# 3MMLedBreakoutForArduino.net
KiCad netlist of a schematic drawn in EAGLE
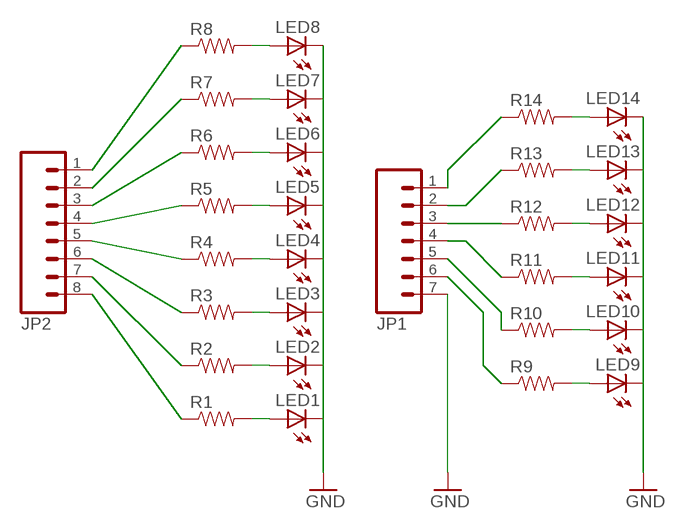
[diagram p0: schematic, sheet 1]

(export (version "E")
  (design (tool "Eeschema 10.0.6"))
  (components
    (comp (ref "JP1")
      (value "M07")
      (footprint "eagle-import:1X07")
      (libsource (lib "eagle-import") (part "M07"))
    )
    (comp (ref "JP2")
      (value "M081X08")
      (footprint "eagle-import:1X08")
      (libsource (lib "eagle-import") (part "M081X08"))
    )
    (comp (ref "LED1")
      (value "LED3MM")
      (footprint "eagle-import:LED3MM")
      (libsource (lib "eagle-import") (part "LED3MM"))
    )
    (comp (ref "LED2")
      (value "LED3MM")
      (footprint "eagle-import:LED3MM")
      (libsource (lib "eagle-import") (part "LED3MM"))
    )
    (comp (ref "LED3")
      (value "LED3MM")
      (footprint "eagle-import:LED3MM")
      (libsource (lib "eagle-import") (part "LED3MM"))
    )
    (comp (ref "LED4")
      (value "LED3MM")
      (footprint "eagle-import:LED3MM")
      (libsource (lib "eagle-import") (part "LED3MM"))
    )
    (comp (ref "LED5")
      (value "LED3MM")
      (footprint "eagle-import:LED3MM")
      (libsource (lib "eagle-import") (part "LED3MM"))
    )
    (comp (ref "LED6")
      (value "LED3MM")
      (footprint "eagle-import:LED3MM")
      (libsource (lib "eagle-import") (part "LED3MM"))
    )
    (comp (ref "LED7")
      (value "LED3MM")
      (footprint "eagle-import:LED3MM")
      (libsource (lib "eagle-import") (part "LED3MM"))
    )
    (comp (ref "LED8")
      (value "LED3MM")
      (footprint "eagle-import:LED3MM")
      (libsource (lib "eagle-import") (part "LED3MM"))
    )
    (comp (ref "LED9")
      (value "LED3MM")
      (footprint "eagle-import:LED3MM")
      (libsource (lib "eagle-import") (part "LED3MM"))
    )
    (comp (ref "LED10")
      (value "LED3MM")
      (footprint "eagle-import:LED3MM")
      (libsource (lib "eagle-import") (part "LED3MM"))
    )
    (comp (ref "LED11")
      (value "LED3MM")
      (footprint "eagle-import:LED3MM")
      (libsource (lib "eagle-import") (part "LED3MM"))
    )
    (comp (ref "LED12")
      (value "LED3MM")
      (footprint "eagle-import:LED3MM")
      (libsource (lib "eagle-import") (part "LED3MM"))
    )
    (comp (ref "LED13")
      (value "LED3MM")
      (footprint "eagle-import:LED3MM")
      (libsource (lib "eagle-import") (part "LED3MM"))
    )
    (comp (ref "LED14")
      (value "LED3MM")
      (footprint "eagle-import:LED3MM")
      (libsource (lib "eagle-import") (part "LED3MM"))
    )
    (comp (ref "R1")
      (value "RESISTORAXIAL-0.3")
      (footprint "eagle-import:AXIAL-0.3")
      (libsource (lib "eagle-import") (part "RESISTORAXIAL-0.3"))
    )
    (comp (ref "R2")
      (value "RESISTORAXIAL-0.3")
      (footprint "eagle-import:AXIAL-0.3")
      (libsource (lib "eagle-import") (part "RESISTORAXIAL-0.3"))
    )
    (comp (ref "R3")
      (value "RESISTORAXIAL-0.3")
      (footprint "eagle-import:AXIAL-0.3")
      (libsource (lib "eagle-import") (part "RESISTORAXIAL-0.3"))
    )
    (comp (ref "R4")
      (value "RESISTORAXIAL-0.3")
      (footprint "eagle-import:AXIAL-0.3")
      (libsource (lib "eagle-import") (part "RESISTORAXIAL-0.3"))
    )
    (comp (ref "R5")
      (value "RESISTORAXIAL-0.3")
      (footprint "eagle-import:AXIAL-0.3")
      (libsource (lib "eagle-import") (part "RESISTORAXIAL-0.3"))
    )
    (comp (ref "R6")
      (value "RESISTORAXIAL-0.3")
      (footprint "eagle-import:AXIAL-0.3")
      (libsource (lib "eagle-import") (part "RESISTORAXIAL-0.3"))
    )
    (comp (ref "R7")
      (value "RESISTORAXIAL-0.3")
      (footprint "eagle-import:AXIAL-0.3")
      (libsource (lib "eagle-import") (part "RESISTORAXIAL-0.3"))
    )
    (comp (ref "R8")
      (value "RESISTORAXIAL-0.3")
      (footprint "eagle-import:AXIAL-0.3")
      (libsource (lib "eagle-import") (part "RESISTORAXIAL-0.3"))
    )
    (comp (ref "R9")
      (value "RESISTORAXIAL-0.3")
      (footprint "eagle-import:AXIAL-0.3")
      (libsource (lib "eagle-import") (part "RESISTORAXIAL-0.3"))
    )
    (comp (ref "R10")
      (value "RESISTORAXIAL-0.3")
      (footprint "eagle-import:AXIAL-0.3")
      (libsource (lib "eagle-import") (part "RESISTORAXIAL-0.3"))
    )
    (comp (ref "R11")
      (value "RESISTORAXIAL-0.3")
      (footprint "eagle-import:AXIAL-0.3")
      (libsource (lib "eagle-import") (part "RESISTORAXIAL-0.3"))
    )
    (comp (ref "R12")
      (value "RESISTORAXIAL-0.3")
      (footprint "eagle-import:AXIAL-0.3")
      (libsource (lib "eagle-import") (part "RESISTORAXIAL-0.3"))
    )
    (comp (ref "R13")
      (value "RESISTORAXIAL-0.3")
      (footprint "eagle-import:AXIAL-0.3")
      (libsource (lib "eagle-import") (part "RESISTORAXIAL-0.3"))
    )
    (comp (ref "R14")
      (value "RESISTORAXIAL-0.3")
      (footprint "eagle-import:AXIAL-0.3")
      (libsource (lib "eagle-import") (part "RESISTORAXIAL-0.3"))
    )
  )
  (nets
    (net (code "1") (name "GND") (class "Default")
      (node (ref "JP1") (pin "7") (pinfunction "7_7") (pintype "passive"))
      (node (ref "LED1") (pin "K") (pinfunction "C_K") (pintype "passive"))
      (node (ref "LED10") (pin "K") (pinfunction "C_K") (pintype "passive"))
      (node (ref "LED11") (pin "K") (pinfunction "C_K") (pintype "passive"))
      (node (ref "LED12") (pin "K") (pinfunction "C_K") (pintype "passive"))
      (node (ref "LED13") (pin "K") (pinfunction "C_K") (pintype "passive"))
      (node (ref "LED14") (pin "K") (pinfunction "C_K") (pintype "passive"))
      (node (ref "LED2") (pin "K") (pinfunction "C_K") (pintype "passive"))
      (node (ref "LED3") (pin "K") (pinfunction "C_K") (pintype "passive"))
      (node (ref "LED4") (pin "K") (pinfunction "C_K") (pintype "passive"))
      (node (ref "LED5") (pin "K") (pinfunction "C_K") (pintype "passive"))
      (node (ref "LED6") (pin "K") (pinfunction "C_K") (pintype "passive"))
      (node (ref "LED7") (pin "K") (pinfunction "C_K") (pintype "passive"))
      (node (ref "LED8") (pin "K") (pinfunction "C_K") (pintype "passive"))
      (node (ref "LED9") (pin "K") (pinfunction "C_K") (pintype "passive"))
    )
    (net (code "2") (name "Net-(R1-1)") (class "Default")
      (node (ref "JP2") (pin "8") (pinfunction "8_8") (pintype "passive"))
      (node (ref "R1") (pin "P$1") (pinfunction "1_P$1") (pintype "passive"))
    )
    (net (code "3") (name "Net-(R1-2)") (class "Default")
      (node (ref "LED1") (pin "A") (pinfunction "A_A") (pintype "passive"))
      (node (ref "R1") (pin "P$2") (pinfunction "2_P$2") (pintype "passive"))
    )
    (net (code "4") (name "Net-(R2-1)") (class "Default")
      (node (ref "JP2") (pin "7") (pinfunction "7_7") (pintype "passive"))
      (node (ref "R2") (pin "P$1") (pinfunction "1_P$1") (pintype "passive"))
    )
    (net (code "5") (name "Net-(R2-2)") (class "Default")
      (node (ref "LED2") (pin "A") (pinfunction "A_A") (pintype "passive"))
      (node (ref "R2") (pin "P$2") (pinfunction "2_P$2") (pintype "passive"))
    )
    (net (code "6") (name "Net-(R3-1)") (class "Default")
      (node (ref "JP2") (pin "6") (pinfunction "6_6") (pintype "passive"))
      (node (ref "R3") (pin "P$1") (pinfunction "1_P$1") (pintype "passive"))
    )
    (net (code "7") (name "Net-(R3-2)") (class "Default")
      (node (ref "LED3") (pin "A") (pinfunction "A_A") (pintype "passive"))
      (node (ref "R3") (pin "P$2") (pinfunction "2_P$2") (pintype "passive"))
    )
    (net (code "8") (name "Net-(R4-1)") (class "Default")
      (node (ref "JP2") (pin "5") (pinfunction "5_5") (pintype "passive"))
      (node (ref "R4") (pin "P$1") (pinfunction "1_P$1") (pintype "passive"))
    )
    (net (code "9") (name "Net-(R4-2)") (class "Default")
      (node (ref "LED4") (pin "A") (pinfunction "A_A") (pintype "passive"))
      (node (ref "R4") (pin "P$2") (pinfunction "2_P$2") (pintype "passive"))
    )
    (net (code "10") (name "Net-(R5-1)") (class "Default")
      (node (ref "JP2") (pin "4") (pinfunction "4_4") (pintype "passive"))
      (node (ref "R5") (pin "P$1") (pinfunction "1_P$1") (pintype "passive"))
    )
    (net (code "11") (name "Net-(R5-2)") (class "Default")
      (node (ref "LED5") (pin "A") (pinfunction "A_A") (pintype "passive"))
      (node (ref "R5") (pin "P$2") (pinfunction "2_P$2") (pintype "passive"))
    )
    (net (code "12") (name "Net-(R6-1)") (class "Default")
      (node (ref "JP2") (pin "3") (pinfunction "3_3") (pintype "passive"))
      (node (ref "R6") (pin "P$1") (pinfunction "1_P$1") (pintype "passive"))
    )
    (net (code "13") (name "Net-(R6-2)") (class "Default")
      (node (ref "LED6") (pin "A") (pinfunction "A_A") (pintype "passive"))
      (node (ref "R6") (pin "P$2") (pinfunction "2_P$2") (pintype "passive"))
    )
    (net (code "14") (name "Net-(R7-1)") (class "Default")
      (node (ref "JP2") (pin "2") (pinfunction "2_2") (pintype "passive"))
      (node (ref "R7") (pin "P$1") (pinfunction "1_P$1") (pintype "passive"))
    )
    (net (code "15") (name "Net-(R7-2)") (class "Default")
      (node (ref "LED7") (pin "A") (pinfunction "A_A") (pintype "passive"))
      (node (ref "R7") (pin "P$2") (pinfunction "2_P$2") (pintype "passive"))
    )
    (net (code "16") (name "Net-(R8-1)") (class "Default")
      (node (ref "JP2") (pin "1") (pinfunction "1_1") (pintype "passive"))
      (node (ref "R8") (pin "P$1") (pinfunction "1_P$1") (pintype "passive"))
    )
    (net (code "17") (name "Net-(R8-2)") (class "Default")
      (node (ref "LED8") (pin "A") (pinfunction "A_A") (pintype "passive"))
      (node (ref "R8") (pin "P$2") (pinfunction "2_P$2") (pintype "passive"))
    )
    (net (code "18") (name "Net-(R9-1)") (class "Default")
      (node (ref "JP1") (pin "6") (pinfunction "6_6") (pintype "passive"))
      (node (ref "R9") (pin "P$1") (pinfunction "1_P$1") (pintype "passive"))
    )
    (net (code "19") (name "Net-(R9-2)") (class "Default")
      (node (ref "LED9") (pin "A") (pinfunction "A_A") (pintype "passive"))
      (node (ref "R9") (pin "P$2") (pinfunction "2_P$2") (pintype "passive"))
    )
    (net (code "20") (name "Net-(R10-1)") (class "Default")
      (node (ref "JP1") (pin "5") (pinfunction "5_5") (pintype "passive"))
      (node (ref "R10") (pin "P$1") (pinfunction "1_P$1") (pintype "passive"))
    )
    (net (code "21") (name "Net-(R10-2)") (class "Default")
      (node (ref "LED10") (pin "A") (pinfunction "A_A") (pintype "passive"))
      (node (ref "R10") (pin "P$2") (pinfunction "2_P$2") (pintype "passive"))
    )
    (net (code "22") (name "Net-(R11-1)") (class "Default")
      (node (ref "JP1") (pin "4") (pinfunction "4_4") (pintype "passive"))
      (node (ref "R11") (pin "P$1") (pinfunction "1_P$1") (pintype "passive"))
    )
    (net (code "23") (name "Net-(R11-2)") (class "Default")
      (node (ref "LED11") (pin "A") (pinfunction "A_A") (pintype "passive"))
      (node (ref "R11") (pin "P$2") (pinfunction "2_P$2") (pintype "passive"))
    )
    (net (code "24") (name "Net-(R12-1)") (class "Default")
      (node (ref "JP1") (pin "3") (pinfunction "3_3") (pintype "passive"))
      (node (ref "R12") (pin "P$1") (pinfunction "1_P$1") (pintype "passive"))
    )
    (net (code "25") (name "Net-(R12-2)") (class "Default")
      (node (ref "LED12") (pin "A") (pinfunction "A_A") (pintype "passive"))
      (node (ref "R12") (pin "P$2") (pinfunction "2_P$2") (pintype "passive"))
    )
    (net (code "26") (name "Net-(R13-1)") (class "Default")
      (node (ref "JP1") (pin "2") (pinfunction "2_2") (pintype "passive"))
      (node (ref "R13") (pin "P$1") (pinfunction "1_P$1") (pintype "passive"))
    )
    (net (code "27") (name "Net-(R13-2)") (class "Default")
      (node (ref "LED13") (pin "A") (pinfunction "A_A") (pintype "passive"))
      (node (ref "R13") (pin "P$2") (pinfunction "2_P$2") (pintype "passive"))
    )
    (net (code "28") (name "Net-(R14-1)") (class "Default")
      (node (ref "JP1") (pin "1") (pinfunction "1_1") (pintype "passive"))
      (node (ref "R14") (pin "P$1") (pinfunction "1_P$1") (pintype "passive"))
    )
    (net (code "29") (name "Net-(R14-2)") (class "Default")
      (node (ref "LED14") (pin "A") (pinfunction "A_A") (pintype "passive"))
      (node (ref "R14") (pin "P$2") (pinfunction "2_P$2") (pintype "passive"))
    )
  )
)
